# CAN.net
KiCad netlist of a schematic drawn in Altium Designer
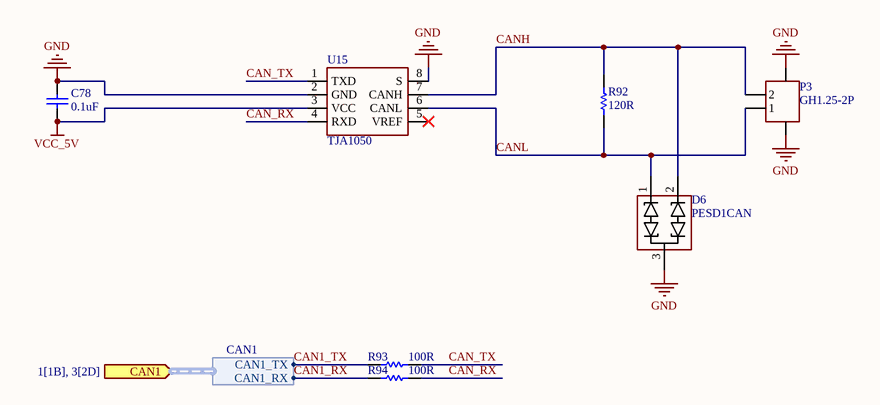
[diagram p0: CAN.SchDoc]

(export (version "E")
  (design (tool "Eeschema 10.0.6"))
  (components
    (comp (ref "C78")
      (value "0.1uF")
      (footprint "C0603_NS")
      (description "Capacitor")
      (libsource (lib "Miscellaneous Devices") (part "Cap"))
    )
    (comp (ref "D6")
      (value "PESD1CAN")
      (footprint "SOT23-3N")
      (libsource (lib "my_library") (part "PESD1CAN"))
    )
    (comp (ref "P3")
      (value "GH1.25-2P")
      (footprint "A1257WR-S-2P")
      (libsource (lib "my_library") (part "Header2"))
    )
    (comp (ref "R92")
      (value "120R")
      (footprint "R0603_NS")
      (description "Resistor")
      (libsource (lib "Miscellaneous Devices") (part "Res1"))
    )
    (comp (ref "R93")
      (value "100R")
      (footprint "R0603_NS")
      (description "Resistor")
      (libsource (lib "Miscellaneous Devices") (part "Res1"))
    )
    (comp (ref "R94")
      (value "100R")
      (footprint "R0603_NS")
      (description "Resistor")
      (libsource (lib "Miscellaneous Devices") (part "Res1"))
    )
    (comp (ref "U15") (value "TJA1050") (footprint "SOP8_N") (libsource (lib "my_library") (part "TJA1050")))
  )
  (nets
    (net (code "2") (name "/CAN1_RX") (class "Default")
      (node (ref "R94") (pin "1") (pinfunction "1_1") (pintype "passive"))
    )
    (net (code "3") (name "/CAN1_TX") (class "Default")
      (node (ref "R93") (pin "1") (pinfunction "1_1") (pintype "passive"))
    )
    (net (code "4") (name "/CANH") (class "Default")
      (node (ref "D6") (pin "2") (pinfunction "2_2") (pintype "passive"))
      (node (ref "P3") (pin "2") (pinfunction "2_2") (pintype "passive"))
      (node (ref "R92") (pin "2") (pinfunction "2_2") (pintype "passive"))
      (node (ref "U15") (pin "7") (pinfunction "CANH_7") (pintype "passive"))
    )
    (net (code "5") (name "/CANL") (class "Default")
      (node (ref "D6") (pin "1") (pinfunction "1_1") (pintype "passive"))
      (node (ref "P3") (pin "1") (pinfunction "1_1") (pintype "passive"))
      (node (ref "R92") (pin "1") (pinfunction "1_1") (pintype "passive"))
      (node (ref "U15") (pin "6") (pinfunction "CANL_6") (pintype "passive"))
    )
    (net (code "6") (name "/CAN_RX") (class "Default")
      (node (ref "R94") (pin "2") (pinfunction "2_2") (pintype "passive"))
      (node (ref "U15") (pin "4") (pinfunction "RXD_4") (pintype "passive"))
    )
    (net (code "7") (name "/CAN_TX") (class "Default")
      (node (ref "R93") (pin "2") (pinfunction "2_2") (pintype "passive"))
      (node (ref "U15") (pin "1") (pinfunction "TXD_1") (pintype "passive"))
    )
    (net (code "9") (name "GND") (class "Default")
      (node (ref "C78") (pin "2") (pinfunction "2_2") (pintype "passive"))
      (node (ref "D6") (pin "3") (pinfunction "3_3") (pintype "passive"))
      (node (ref "P3") (pin "0") (pinfunction "0_0") (pintype "passive"))
      (node (ref "U15") (pin "2") (pinfunction "GND_2") (pintype "passive"))
      (node (ref "U15") (pin "8") (pinfunction "S_8") (pintype "passive"))
    )
    (net (code "10") (name "VCC_5V") (class "Default")
      (node (ref "C78") (pin "1") (pinfunction "1_1") (pintype "passive"))
      (node (ref "U15") (pin "3") (pinfunction "VCC_3") (pintype "passive"))
    )
    (net (code "11") (name "unconnected-(U15-VREF-Pad5)") (class "Default")
      (node (ref "U15") (pin "5") (pinfunction "VREF_5") (pintype "passive+no_connect"))
    )
  )
)
